# main_pcb.net
KiCad netlist of a schematic drawn in EAGLE
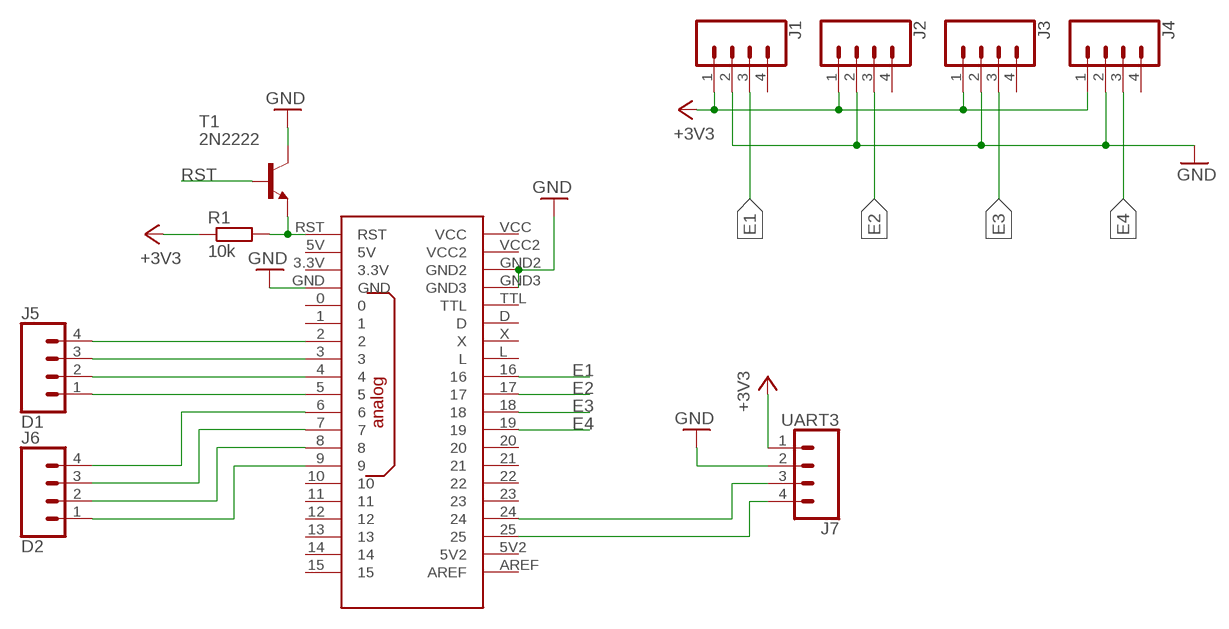
[diagram p0: schematic, sheet 1]

(export (version "E")
  (design (tool "Eeschema 10.0.6"))
  (components
    (comp (ref "J1")
      (value "CONN_04JST-PTH")
      (footprint "eagle-import:JST-4-PTH")
      (libsource (lib "eagle-import") (part "CONN_04JST-PTH"))
    )
    (comp (ref "J2")
      (value "CONN_04JST-PTH")
      (footprint "eagle-import:JST-4-PTH")
      (libsource (lib "eagle-import") (part "CONN_04JST-PTH"))
    )
    (comp (ref "J3")
      (value "CONN_04JST-PTH")
      (footprint "eagle-import:JST-4-PTH")
      (libsource (lib "eagle-import") (part "CONN_04JST-PTH"))
    )
    (comp (ref "J4")
      (value "CONN_04JST-PTH")
      (footprint "eagle-import:JST-4-PTH")
      (libsource (lib "eagle-import") (part "CONN_04JST-PTH"))
    )
    (comp (ref "J5")
      (value "D1")
      (footprint "eagle-import:JST-4-PTH")
      (libsource (lib "eagle-import") (part "CONN_04JST-PTH"))
    )
    (comp (ref "J6")
      (value "D2")
      (footprint "eagle-import:JST-4-PTH")
      (libsource (lib "eagle-import") (part "CONN_04JST-PTH"))
    )
    (comp (ref "J7")
      (value "UART3")
      (footprint "eagle-import:1X04")
      (libsource (lib "eagle-import") (part "CONN_04"))
    )
    (comp (ref "R1")
      (value "10k")
      (footprint "eagle-import:0204_7")
      (libsource (lib "eagle-import") (part "R-EU_0204/7"))
    )
    (comp (ref "T1")
      (value "2N2222")
      (footprint "eagle-import:TO18")
      (libsource (lib "eagle-import") (part "2N2222"))
    )
    (comp (ref "U$1")
      (value "OPENCM9.04")
      (footprint "eagle-import:OPENCM9.04")
      (libsource (lib "eagle-import") (part "OPENCM9.04"))
    )
  )
  (nets
    (net (code "1") (name "+3V3") (class "Default")
      (node (ref "J1") (pin "1") (pinfunction "1_1") (pintype "passive"))
      (node (ref "J2") (pin "1") (pinfunction "1_1") (pintype "passive"))
      (node (ref "J3") (pin "1") (pinfunction "1_1") (pintype "passive"))
      (node (ref "J4") (pin "1") (pinfunction "1_1") (pintype "passive"))
      (node (ref "J7") (pin "1") (pinfunction "1_1") (pintype "passive"))
      (node (ref "R1") (pin "1") (pinfunction "1_1") (pintype "passive"))
    )
    (net (code "2") (name "/RST") (class "Default")
      (node (ref "T1") (pin "2") (pinfunction "B_2") (pintype "passive"))
    )
    (net (code "3") (name "E1") (class "Default")
      (node (ref "J1") (pin "3") (pinfunction "3_3") (pintype "passive"))
      (node (ref "U$1") (pin "16") (pinfunction "16_16") (pintype "bidirectional"))
    )
    (net (code "4") (name "E2") (class "Default")
      (node (ref "J2") (pin "3") (pinfunction "3_3") (pintype "passive"))
      (node (ref "U$1") (pin "17") (pinfunction "17_17") (pintype "bidirectional"))
    )
    (net (code "5") (name "E3") (class "Default")
      (node (ref "J3") (pin "3") (pinfunction "3_3") (pintype "passive"))
      (node (ref "U$1") (pin "18") (pinfunction "18_18") (pintype "bidirectional"))
    )
    (net (code "6") (name "E4") (class "Default")
      (node (ref "J4") (pin "3") (pinfunction "3_3") (pintype "passive"))
      (node (ref "U$1") (pin "19") (pinfunction "19_19") (pintype "bidirectional"))
    )
    (net (code "7") (name "GND") (class "Default")
      (node (ref "J1") (pin "2") (pinfunction "2_2") (pintype "passive"))
      (node (ref "J2") (pin "2") (pinfunction "2_2") (pintype "passive"))
      (node (ref "J3") (pin "2") (pinfunction "2_2") (pintype "passive"))
      (node (ref "J4") (pin "2") (pinfunction "2_2") (pintype "passive"))
      (node (ref "J7") (pin "2") (pinfunction "2_2") (pintype "passive"))
      (node (ref "T1") (pin "3") (pinfunction "C_3") (pintype "passive"))
      (node (ref "U$1") (pin "GND") (pinfunction "GND_GND") (pintype "bidirectional"))
      (node (ref "U$1") (pin "GND2") (pinfunction "GND2_GND2") (pintype "bidirectional"))
      (node (ref "U$1") (pin "GND3") (pinfunction "GND3_GND3") (pintype "bidirectional"))
    )
    (net (code "8") (name "Net-(J5-Pad1)") (class "Default")
      (node (ref "J5") (pin "1") (pinfunction "1_1") (pintype "passive"))
      (node (ref "U$1") (pin "5") (pinfunction "5_5") (pintype "bidirectional"))
    )
    (net (code "9") (name "Net-(J5-Pad2)") (class "Default")
      (node (ref "J5") (pin "2") (pinfunction "2_2") (pintype "passive"))
      (node (ref "U$1") (pin "4") (pinfunction "4_4") (pintype "bidirectional"))
    )
    (net (code "10") (name "Net-(J5-Pad3)") (class "Default")
      (node (ref "J5") (pin "3") (pinfunction "3_3") (pintype "passive"))
      (node (ref "U$1") (pin "3") (pinfunction "3_3") (pintype "bidirectional"))
    )
    (net (code "11") (name "Net-(J5-Pad4)") (class "Default")
      (node (ref "J5") (pin "4") (pinfunction "4_4") (pintype "passive"))
      (node (ref "U$1") (pin "2") (pinfunction "2_2") (pintype "bidirectional"))
    )
    (net (code "12") (name "Net-(J6-Pad1)") (class "Default")
      (node (ref "J6") (pin "1") (pinfunction "1_1") (pintype "passive"))
      (node (ref "U$1") (pin "9") (pinfunction "9_9") (pintype "bidirectional"))
    )
    (net (code "13") (name "Net-(J6-Pad2)") (class "Default")
      (node (ref "J6") (pin "2") (pinfunction "2_2") (pintype "passive"))
      (node (ref "U$1") (pin "8") (pinfunction "8_8") (pintype "bidirectional"))
    )
    (net (code "14") (name "Net-(J6-Pad3)") (class "Default")
      (node (ref "J6") (pin "3") (pinfunction "3_3") (pintype "passive"))
      (node (ref "U$1") (pin "7") (pinfunction "7_7") (pintype "bidirectional"))
    )
    (net (code "15") (name "Net-(J6-Pad4)") (class "Default")
      (node (ref "J6") (pin "4") (pinfunction "4_4") (pintype "passive"))
      (node (ref "U$1") (pin "6") (pinfunction "6_6") (pintype "bidirectional"))
    )
    (net (code "16") (name "Net-(J7-Pad3)") (class "Default")
      (node (ref "J7") (pin "3") (pinfunction "3_3") (pintype "passive"))
      (node (ref "U$1") (pin "24") (pinfunction "24_24") (pintype "bidirectional"))
    )
    (net (code "17") (name "Net-(J7-Pad4)") (class "Default")
      (node (ref "J7") (pin "4") (pinfunction "4_4") (pintype "passive"))
      (node (ref "U$1") (pin "25") (pinfunction "25_25") (pintype "bidirectional"))
    )
    (net (code "18") (name "Net-(T1-E)") (class "Default")
      (node (ref "R1") (pin "2") (pinfunction "2_2") (pintype "passive"))
      (node (ref "T1") (pin "1") (pinfunction "E_1") (pintype "passive"))
      (node (ref "U$1") (pin "RST") (pinfunction "RST_RST") (pintype "bidirectional"))
    )
    (net (code "19") (name "unconnected-(J1-Pad4)") (class "Default")
      (node (ref "J1") (pin "4") (pinfunction "4_4") (pintype "passive"))
    )
    (net (code "20") (name "unconnected-(J2-Pad4)") (class "Default")
      (node (ref "J2") (pin "4") (pinfunction "4_4") (pintype "passive"))
    )
    (net (code "21") (name "unconnected-(J3-Pad4)") (class "Default")
      (node (ref "J3") (pin "4") (pinfunction "4_4") (pintype "passive"))
    )
    (net (code "22") (name "unconnected-(J4-Pad4)") (class "Default")
      (node (ref "J4") (pin "4") (pinfunction "4_4") (pintype "passive"))
    )
    (net (code "23") (name "unconnected-(U$1-Pad0)") (class "Default")
      (node (ref "U$1") (pin "0") (pinfunction "0_0") (pintype "bidirectional"))
    )
    (net (code "24") (name "unconnected-(U$1-Pad1)") (class "Default")
      (node (ref "U$1") (pin "1") (pinfunction "1_1") (pintype "bidirectional"))
    )
    (net (code "25") (name "unconnected-(U$1-Pad3.3V)") (class "Default")
      (node (ref "U$1") (pin "3.3V") (pinfunction "3.3V_3.3V") (pintype "bidirectional"))
    )
    (net (code "26") (name "unconnected-(U$1-Pad5V)") (class "Default")
      (node (ref "U$1") (pin "5V") (pinfunction "5V_5V") (pintype "bidirectional"))
    )
    (net (code "27") (name "unconnected-(U$1-Pad5V2)") (class "Default")
      (node (ref "U$1") (pin "5V2") (pinfunction "5V2_5V2") (pintype "bidirectional"))
    )
    (net (code "28") (name "unconnected-(U$1-Pad10)") (class "Default")
      (node (ref "U$1") (pin "10") (pinfunction "10_10") (pintype "bidirectional"))
    )
    (net (code "29") (name "unconnected-(U$1-Pad11)") (class "Default")
      (node (ref "U$1") (pin "11") (pinfunction "11_11") (pintype "bidirectional"))
    )
    (net (code "30") (name "unconnected-(U$1-Pad12)") (class "Default")
      (node (ref "U$1") (pin "12") (pinfunction "12_12") (pintype "bidirectional"))
    )
    (net (code "31") (name "unconnected-(U$1-Pad13)") (class "Default")
      (node (ref "U$1") (pin "13") (pinfunction "13_13") (pintype "bidirectional"))
    )
    (net (code "32") (name "unconnected-(U$1-Pad14)") (class "Default")
      (node (ref "U$1") (pin "14") (pinfunction "14_14") (pintype "bidirectional"))
    )
    (net (code "33") (name "unconnected-(U$1-Pad15)") (class "Default")
      (node (ref "U$1") (pin "15") (pinfunction "15_15") (pintype "bidirectional"))
    )
    (net (code "34") (name "unconnected-(U$1-Pad20)") (class "Default")
      (node (ref "U$1") (pin "20") (pinfunction "20_20") (pintype "bidirectional"))
    )
    (net (code "35") (name "unconnected-(U$1-Pad21)") (class "Default")
      (node (ref "U$1") (pin "21") (pinfunction "21_21") (pintype "bidirectional"))
    )
    (net (code "36") (name "unconnected-(U$1-Pad22)") (class "Default")
      (node (ref "U$1") (pin "22") (pinfunction "22_22") (pintype "bidirectional"))
    )
    (net (code "37") (name "unconnected-(U$1-Pad23)") (class "Default")
      (node (ref "U$1") (pin "23") (pinfunction "23_23") (pintype "bidirectional"))
    )
    (net (code "38") (name "unconnected-(U$1-PadAREF)") (class "Default")
      (node (ref "U$1") (pin "AREF") (pinfunction "AREF_AREF") (pintype "bidirectional"))
    )
    (net (code "39") (name "unconnected-(U$1-PadD)") (class "Default")
      (node (ref "U$1") (pin "D") (pinfunction "D_D") (pintype "bidirectional"))
    )
    (net (code "40") (name "unconnected-(U$1-PadL)") (class "Default")
      (node (ref "U$1") (pin "L") (pinfunction "L_L") (pintype "bidirectional"))
    )
    (net (code "41") (name "unconnected-(U$1-PadTTL)") (class "Default")
      (node (ref "U$1") (pin "TTL") (pinfunction "TTL_TTL") (pintype "bidirectional"))
    )
    (net (code "42") (name "unconnected-(U$1-PadVCC)") (class "Default")
      (node (ref "U$1") (pin "VCC") (pinfunction "VCC_VCC") (pintype "bidirectional"))
    )
    (net (code "43") (name "unconnected-(U$1-PadVCC2)") (class "Default")
      (node (ref "U$1") (pin "VCC2") (pinfunction "VCC2_VCC2") (pintype "bidirectional"))
    )
    (net (code "44") (name "unconnected-(U$1-PadX)") (class "Default")
      (node (ref "U$1") (pin "X") (pinfunction "X_X") (pintype "bidirectional"))
    )
  )
)
